# SCH_New-Project_2024-06-18.net
KiCad netlist of a schematic drawn in EasyEDA
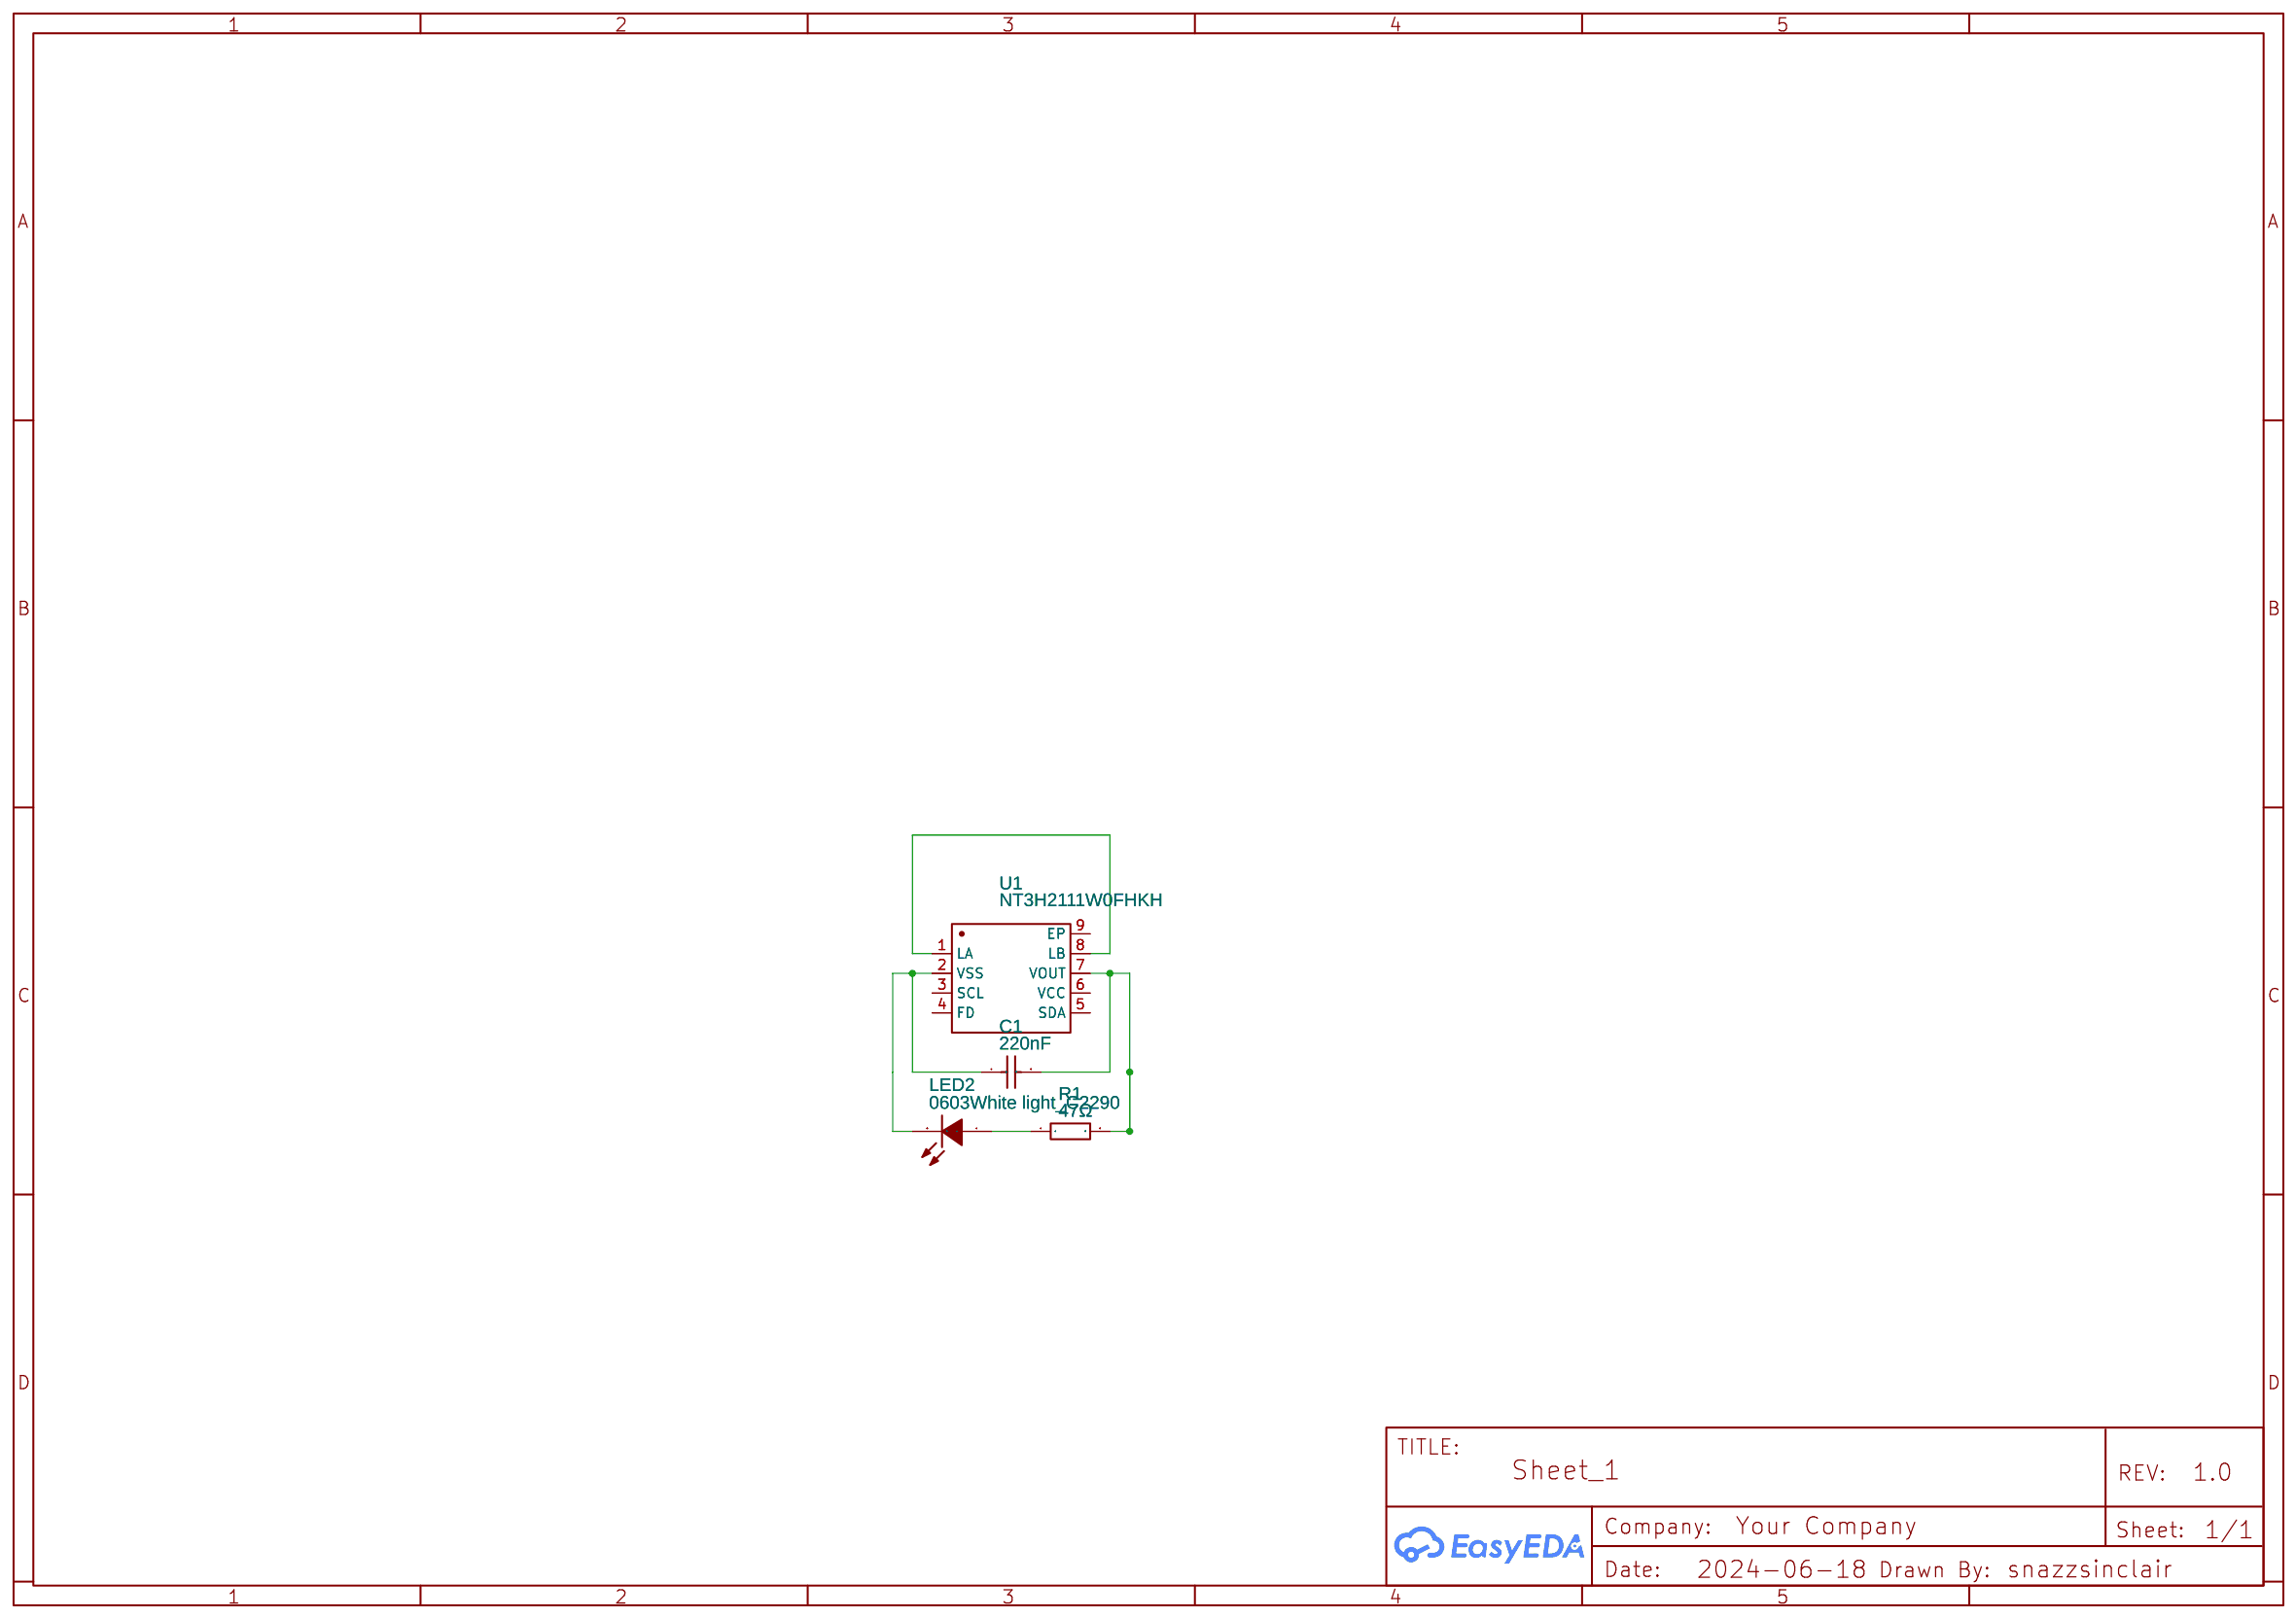
[diagram p0: schematic sheet]

(export (version "E")
  (design (tool "Eeschema 10.0.6"))
  (components
    (comp (ref "C1")
      (value "220nF")
      (fields
        (field (name "Manufacturer Part") "CL10B224KA8NNNC")
        (field (name "Manufacturer") "SAMSUNG(三星)")
      )
      (libsource (lib "") (part "CL10B224KA8NNNC"))
    )
    (comp (ref "LED2")
      (value "0603White light_C2290")
      (fields (field (name "Manufacturer Part") "KT-0603白灯") (field (name "Manufacturer") "KENTO"))
      (libsource (lib "") (part "0603White light_C2290"))
    )
    (comp (ref "R1")
      (value "47Ω")
      (fields
        (field (name "Manufacturer Part") "0603WAF470JT5E")
        (field (name "Manufacturer") "UNI-ROYAL(厚声)")
      )
      (libsource (lib "") (part "0603WAF470JT5E"))
    )
    (comp (ref "U1")
      (value "NT3H2111W0FHKH")
      (fields (field (name "Manufacturer") "NXP(恩智浦)"))
      (libsource (lib "") (part "NT3H2111W0FHKH"))
    )
  )
  (nets
    (net (code "1") (name "Net-(LED2-A)") (class "Default")
      (node (ref "LED2") (pin "1") (pinfunction "A_1") (pintype "unspecified"))
      (node (ref "R1") (pin "1") (pinfunction "1_1") (pintype "input"))
    )
    (net (code "2") (name "Net-(LED2-K)") (class "Default")
      (node (ref "C1") (pin "1") (pinfunction "1_1") (pintype "input"))
      (node (ref "LED2") (pin "2") (pinfunction "K_2") (pintype "unspecified"))
      (node (ref "U1") (pin "2") (pinfunction "VSS_2") (pintype "unspecified"))
    )
    (net (code "3") (name "Net-(U1-LA)") (class "Default")
      (node (ref "U1") (pin "1") (pinfunction "LA_1") (pintype "unspecified"))
      (node (ref "U1") (pin "8") (pinfunction "LB_8") (pintype "unspecified"))
    )
    (net (code "4") (name "Net-(U1-VOUT)") (class "Default")
      (node (ref "C1") (pin "2") (pinfunction "2_2") (pintype "input"))
      (node (ref "R1") (pin "2") (pinfunction "2_2") (pintype "input"))
      (node (ref "U1") (pin "7") (pinfunction "VOUT_7") (pintype "unspecified"))
    )
    (net (code "5") (name "unconnected-(U1-EP-Pad9)") (class "Default")
      (node (ref "U1") (pin "9") (pinfunction "EP_9") (pintype "unspecified"))
    )
    (net (code "6") (name "unconnected-(U1-FD-Pad4)") (class "Default")
      (node (ref "U1") (pin "4") (pinfunction "FD_4") (pintype "unspecified"))
    )
    (net (code "7") (name "unconnected-(U1-SCL-Pad3)") (class "Default")
      (node (ref "U1") (pin "3") (pinfunction "SCL_3") (pintype "unspecified"))
    )
    (net (code "8") (name "unconnected-(U1-SDA-Pad5)") (class "Default")
      (node (ref "U1") (pin "5") (pinfunction "SDA_5") (pintype "unspecified"))
    )
    (net (code "9") (name "unconnected-(U1-VCC-Pad6)") (class "Default")
      (node (ref "U1") (pin "6") (pinfunction "VCC_6") (pintype "unspecified"))
    )
  )
)
